# 03_POWER.net
KiCad netlist of a schematic drawn in Altium Designer
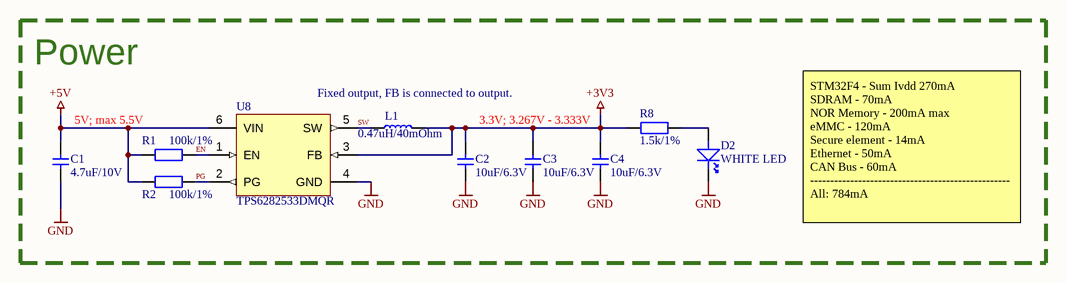
[diagram p0: 03 POWER.SchDoc]

(export (version "E")
  (design (tool "Eeschema 10.0.6"))
  (components
    (comp (ref "C1")
      (value "4.7uF/10V")
      (footprint "CAPC1608X10M-0603")
      (description "4.7 µF ±10% 10V Ceramic Capacitor X7S 0603 (1608 Metric)")
      (fields (field (name "MPN") "GRM188C71A475KE11D"))
      (libsource (lib "Symbol") (part "GRM188C71A475KE11D"))
    )
    (comp (ref "C2")
      (value "10uF/6.3V")
      (footprint "CAPC1005X06M-0402")
      (description "10 µF ±20% 6.3V Ceramic Capacitor X5R 0402 (1005 Metric)")
      (fields (field (name "MPN") "GRM155R60J106ME05J"))
      (libsource (lib "Symbol") (part "GRM155R60J106ME05J"))
    )
    (comp (ref "C3")
      (value "10uF/6.3V")
      (footprint "CAPC1005X06M-0402")
      (description "10 µF ±20% 6.3V Ceramic Capacitor X5R 0402 (1005 Metric)")
      (fields (field (name "MPN") "GRM155R60J106ME05J"))
      (libsource (lib "Symbol") (part "GRM155R60J106ME05J"))
    )
    (comp (ref "C4")
      (value "10uF/6.3V")
      (footprint "CAPC1005X06M-0402")
      (description "10 µF ±20% 6.3V Ceramic Capacitor X5R 0402 (1005 Metric)")
      (fields (field (name "MPN") "GRM155R60J106ME05J"))
      (libsource (lib "Symbol") (part "GRM155R60J106ME05J"))
    )
    (comp (ref "D2")
      (value "WHITE LED")
      (footprint "LED-0402")
      (description "White LED Indication - Discrete 3.1V 0402 (1005 Metric)")
      (fields (field (name "MPN") "QBLP595-IW-2897"))
      (libsource (lib "Symbol") (part "QBLP595-IW-2897"))
    )
    (comp (ref "L1")
      (value "0.47uH/40mOhm")
      (footprint "INDC200x160-2016")
      (description "470 nH Shielded Inductor 3.6 A 40mOhm Max 0806 (2016 Metric)")
      (fields (field (name "MPN") "SRP2010DPA-R47M"))
      (libsource (lib "Symbol") (part "SRP2010DPA-R47M"))
    )
    (comp (ref "R1")
      (value "100k/1%")
      (footprint "RESC1005X04M-0402")
      (description "100 kOhms ±1% 0.063W, 1/16W Chip Resistor 0402 (1005 Metric) Moisture Resistant Thick Film")
      (fields (field (name "MPN") "RC0402FR-07100KL"))
      (libsource (lib "Symbol") (part "RC0402FR-07100KL"))
    )
    (comp (ref "R2")
      (value "100k/1%")
      (footprint "RESC1005X04M-0402")
      (description "100 kOhms ±1% 0.063W, 1/16W Chip Resistor 0402 (1005 Metric) Moisture Resistant Thick Film")
      (fields (field (name "MPN") "RC0402FR-07100KL"))
      (libsource (lib "Symbol") (part "RC0402FR-07100KL"))
    )
    (comp (ref "R8")
      (value "1.5k/1%")
      (footprint "RESC1005X04M-0402")
      (description "1.5 kOhms ±1% 0.063W, 1/16W Chip Resistor 0402 (1005 Metric) Moisture Resistant Thick Film")
      (fields (field (name "MPN") "RC0402FR-071K5L"))
      (libsource (lib "Symbol") (part "RC0402FR-071K5L"))
    )
    (comp (ref "U8")
      (value "TPS6282533DMQR")
      (footprint "VSON-HR (DMQ)")
      (description "Buck Switching Regulator IC Positive Fixed 3.3V 1 Output 2A 6-VFDFN")
      (libsource (lib "Symbol") (part "TPS6282533DMQR"))
    )
  )
  (nets
    (net (code "1") (name "+3V3") (class "Default")
      (node (ref "C2") (pin "2") (pinfunction "2_2") (pintype "passive"))
      (node (ref "C3") (pin "2") (pinfunction "2_2") (pintype "passive"))
      (node (ref "C4") (pin "2") (pinfunction "2_2") (pintype "passive"))
      (node (ref "L1") (pin "2") (pinfunction "2_2") (pintype "passive"))
      (node (ref "R8") (pin "1") (pinfunction "1_1") (pintype "passive"))
      (node (ref "U8") (pin "3") (pinfunction "FB_3") (pintype "input"))
    )
    (net (code "2") (name "+5V") (class "Default")
      (node (ref "C1") (pin "2") (pinfunction "2_2") (pintype "passive"))
      (node (ref "R1") (pin "2") (pinfunction "2_2") (pintype "passive"))
      (node (ref "R2") (pin "2") (pinfunction "2_2") (pintype "passive"))
      (node (ref "U8") (pin "6") (pinfunction "VIN_6") (pintype "power_in"))
    )
    (net (code "3") (name "/EN") (class "Default")
      (node (ref "R1") (pin "1") (pinfunction "1_1") (pintype "passive"))
      (node (ref "U8") (pin "1") (pinfunction "EN_1") (pintype "input"))
    )
    (net (code "4") (name "/PG") (class "Default")
      (node (ref "R2") (pin "1") (pinfunction "1_1") (pintype "passive"))
      (node (ref "U8") (pin "2") (pinfunction "PG_2") (pintype "output"))
    )
    (net (code "5") (name "/SW") (class "Default")
      (node (ref "L1") (pin "1") (pinfunction "1_1") (pintype "passive"))
      (node (ref "U8") (pin "5") (pinfunction "SW_5") (pintype "output"))
    )
    (net (code "6") (name "GND") (class "Default")
      (node (ref "C1") (pin "1") (pinfunction "1_1") (pintype "passive"))
      (node (ref "C2") (pin "1") (pinfunction "1_1") (pintype "passive"))
      (node (ref "C3") (pin "1") (pinfunction "1_1") (pintype "passive"))
      (node (ref "C4") (pin "1") (pinfunction "1_1") (pintype "passive"))
      (node (ref "D2") (pin "1") (pinfunction "1_1") (pintype "passive"))
      (node (ref "U8") (pin "4") (pinfunction "GND_4") (pintype "power_in"))
    )
    (net (code "7") (name "Net-(D2-Pad2)") (class "Default")
      (node (ref "D2") (pin "2") (pinfunction "2_2") (pintype "passive"))
      (node (ref "R8") (pin "2") (pinfunction "2_2") (pintype "passive"))
    )
  )
)
